# Power_board_2.net
KiCad netlist of a schematic drawn in Altium Designer
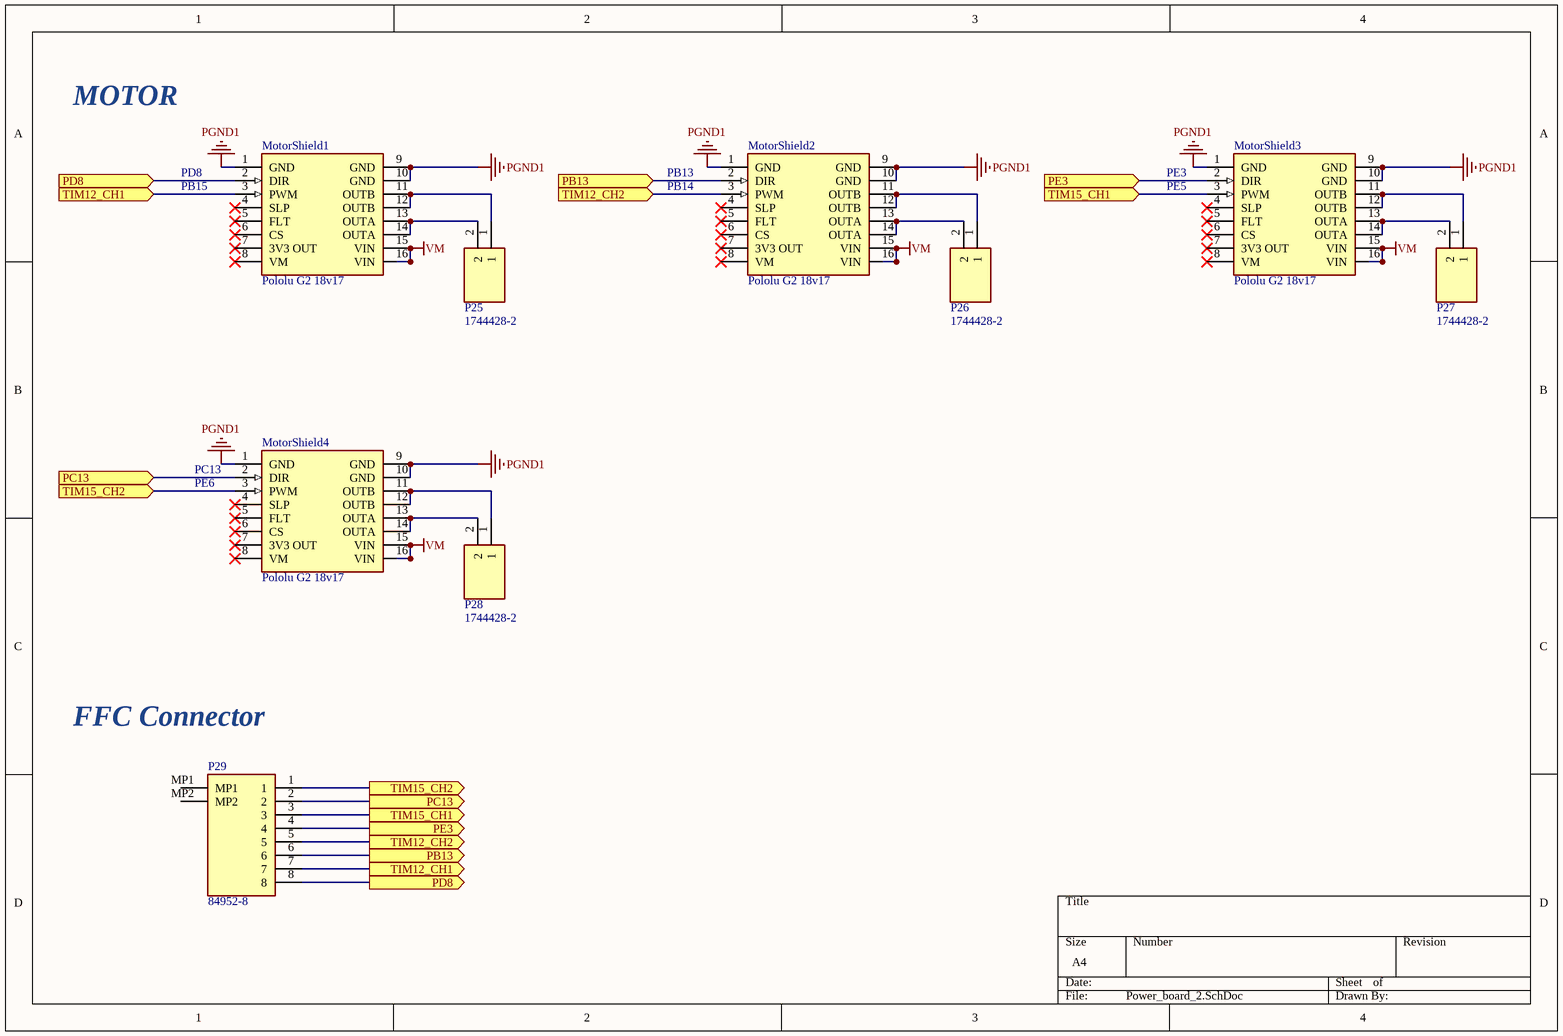
[diagram p0: Power_board_2.SchDoc]

(export (version "E")
  (design (tool "Eeschema 10.0.6"))
  (components
    (comp (ref "MotorShield1")
      (value "Pololu G2 18v17")
      (footprint "SamacSys:Pololu G218V17")
      (description "DC Motor Driver")
      (libsource (lib "SamacSys") (part "Pololu G2 18v17"))
    )
    (comp (ref "MotorShield2")
      (value "Pololu G2 18v17")
      (footprint "SamacSys:Pololu G218V17")
      (description "DC Motor Driver")
      (libsource (lib "SamacSys") (part "Pololu G2 18v17"))
    )
    (comp (ref "MotorShield3")
      (value "Pololu G2 18v17")
      (footprint "SamacSys:Pololu G218V17")
      (description "DC Motor Driver")
      (libsource (lib "SamacSys") (part "Pololu G2 18v17"))
    )
    (comp (ref "MotorShield4")
      (value "Pololu G2 18v17")
      (footprint "SamacSys:Pololu G218V17")
      (description "DC Motor Driver")
      (libsource (lib "SamacSys") (part "Pololu G2 18v17"))
    )
    (comp (ref "P25")
      (value "1744428-2")
      (footprint "SamacSys:17444282")
      (description "Connector")
      (fields (field (name "MOUSER PART NUMBER") "571-1744428-2"))
      (libsource (lib "*") (part "1744428-2"))
    )
    (comp (ref "P26")
      (value "1744428-2")
      (footprint "SamacSys:17444282")
      (description "Connector")
      (fields (field (name "MOUSER PART NUMBER") "571-1744428-2"))
      (libsource (lib "*") (part "1744428-2"))
    )
    (comp (ref "P27")
      (value "1744428-2")
      (footprint "SamacSys:17444282")
      (description "Connector")
      (fields (field (name "MOUSER PART NUMBER") "571-1744428-2"))
      (libsource (lib "*") (part "1744428-2"))
    )
    (comp (ref "P28")
      (value "1744428-2")
      (footprint "SamacSys:17444282")
      (description "Connector")
      (fields (field (name "MOUSER PART NUMBER") "571-1744428-2"))
      (libsource (lib "*") (part "1744428-2"))
    )
    (comp (ref "P29")
      (value "84952-8")
      (footprint "SamacSys:849528")
      (description "Connector")
      (fields (field (name "MOUSER PART NUMBER") "571-84952-8"))
      (libsource (lib "*") (part "84952-8"))
    )
  )
  (nets
    (net (code "1") (name "/PB13") (class "Default")
      (node (ref "MotorShield2") (pin "2") (pinfunction "DIR_2") (pintype "input"))
      (node (ref "P29") (pin "6") (pinfunction "6_6") (pintype "passive"))
    )
    (net (code "2") (name "/PC13") (class "Default")
      (node (ref "MotorShield4") (pin "2") (pinfunction "DIR_2") (pintype "input"))
      (node (ref "P29") (pin "2") (pinfunction "2_2") (pintype "passive"))
    )
    (net (code "3") (name "/PD8") (class "Default")
      (node (ref "MotorShield1") (pin "2") (pinfunction "DIR_2") (pintype "input"))
      (node (ref "P29") (pin "8") (pinfunction "8_8") (pintype "passive"))
    )
    (net (code "4") (name "/PE3") (class "Default")
      (node (ref "MotorShield3") (pin "2") (pinfunction "DIR_2") (pintype "input"))
      (node (ref "P29") (pin "4") (pinfunction "4_4") (pintype "passive"))
    )
    (net (code "5") (name "/TIM12_CH1") (class "Default")
      (node (ref "MotorShield1") (pin "3") (pinfunction "PWM_3") (pintype "input"))
      (node (ref "P29") (pin "7") (pinfunction "7_7") (pintype "passive"))
    )
    (net (code "6") (name "/TIM12_CH2") (class "Default")
      (node (ref "MotorShield2") (pin "3") (pinfunction "PWM_3") (pintype "input"))
      (node (ref "P29") (pin "5") (pinfunction "5_5") (pintype "passive"))
    )
    (net (code "7") (name "/TIM15_CH1") (class "Default")
      (node (ref "MotorShield3") (pin "3") (pinfunction "PWM_3") (pintype "input"))
      (node (ref "P29") (pin "3") (pinfunction "3_3") (pintype "passive"))
    )
    (net (code "8") (name "/TIM15_CH2") (class "Default")
      (node (ref "MotorShield4") (pin "3") (pinfunction "PWM_3") (pintype "input"))
      (node (ref "P29") (pin "1") (pinfunction "1_1") (pintype "passive"))
    )
    (net (code "9") (name "Net-(MotorShield1-OUTA-Pad13)") (class "Default")
      (node (ref "MotorShield1") (pin "13") (pinfunction "OUTA_13") (pintype "tri_state"))
      (node (ref "MotorShield1") (pin "14") (pinfunction "OUTA_14") (pintype "tri_state"))
      (node (ref "P25") (pin "2") (pinfunction "2_2") (pintype "passive"))
    )
    (net (code "10") (name "Net-(MotorShield1-OUTB-Pad11)") (class "Default")
      (node (ref "MotorShield1") (pin "11") (pinfunction "OUTB_11") (pintype "tri_state"))
      (node (ref "MotorShield1") (pin "12") (pinfunction "OUTB_12") (pintype "tri_state"))
      (node (ref "P25") (pin "1") (pinfunction "1_1") (pintype "passive"))
    )
    (net (code "11") (name "Net-(MotorShield2-OUTA-Pad13)") (class "Default")
      (node (ref "MotorShield2") (pin "13") (pinfunction "OUTA_13") (pintype "tri_state"))
      (node (ref "MotorShield2") (pin "14") (pinfunction "OUTA_14") (pintype "tri_state"))
      (node (ref "P26") (pin "2") (pinfunction "2_2") (pintype "passive"))
    )
    (net (code "12") (name "Net-(MotorShield2-OUTB-Pad11)") (class "Default")
      (node (ref "MotorShield2") (pin "11") (pinfunction "OUTB_11") (pintype "tri_state"))
      (node (ref "MotorShield2") (pin "12") (pinfunction "OUTB_12") (pintype "tri_state"))
      (node (ref "P26") (pin "1") (pinfunction "1_1") (pintype "passive"))
    )
    (net (code "13") (name "Net-(MotorShield3-OUTA-Pad13)") (class "Default")
      (node (ref "MotorShield3") (pin "13") (pinfunction "OUTA_13") (pintype "tri_state"))
      (node (ref "MotorShield3") (pin "14") (pinfunction "OUTA_14") (pintype "tri_state"))
      (node (ref "P27") (pin "2") (pinfunction "2_2") (pintype "passive"))
    )
    (net (code "14") (name "Net-(MotorShield3-OUTB-Pad11)") (class "Default")
      (node (ref "MotorShield3") (pin "11") (pinfunction "OUTB_11") (pintype "tri_state"))
      (node (ref "MotorShield3") (pin "12") (pinfunction "OUTB_12") (pintype "tri_state"))
      (node (ref "P27") (pin "1") (pinfunction "1_1") (pintype "passive"))
    )
    (net (code "15") (name "Net-(MotorShield4-OUTA-Pad13)") (class "Default")
      (node (ref "MotorShield4") (pin "13") (pinfunction "OUTA_13") (pintype "tri_state"))
      (node (ref "MotorShield4") (pin "14") (pinfunction "OUTA_14") (pintype "tri_state"))
      (node (ref "P28") (pin "2") (pinfunction "2_2") (pintype "passive"))
    )
    (net (code "16") (name "Net-(MotorShield4-OUTB-Pad11)") (class "Default")
      (node (ref "MotorShield4") (pin "11") (pinfunction "OUTB_11") (pintype "tri_state"))
      (node (ref "MotorShield4") (pin "12") (pinfunction "OUTB_12") (pintype "tri_state"))
      (node (ref "P28") (pin "1") (pinfunction "1_1") (pintype "passive"))
    )
    (net (code "17") (name "PGND1") (class "Default")
      (node (ref "MotorShield1") (pin "1") (pinfunction "GND_1") (pintype "tri_state"))
      (node (ref "MotorShield1") (pin "10") (pinfunction "GND_10") (pintype "tri_state"))
      (node (ref "MotorShield1") (pin "9") (pinfunction "GND_9") (pintype "passive"))
      (node (ref "MotorShield2") (pin "1") (pinfunction "GND_1") (pintype "tri_state"))
      (node (ref "MotorShield2") (pin "10") (pinfunction "GND_10") (pintype "tri_state"))
      (node (ref "MotorShield2") (pin "9") (pinfunction "GND_9") (pintype "passive"))
      (node (ref "MotorShield3") (pin "1") (pinfunction "GND_1") (pintype "tri_state"))
      (node (ref "MotorShield3") (pin "10") (pinfunction "GND_10") (pintype "tri_state"))
      (node (ref "MotorShield3") (pin "9") (pinfunction "GND_9") (pintype "passive"))
      (node (ref "MotorShield4") (pin "1") (pinfunction "GND_1") (pintype "tri_state"))
      (node (ref "MotorShield4") (pin "10") (pinfunction "GND_10") (pintype "tri_state"))
      (node (ref "MotorShield4") (pin "9") (pinfunction "GND_9") (pintype "passive"))
    )
    (net (code "18") (name "VM") (class "Default")
      (node (ref "MotorShield1") (pin "15") (pinfunction "VIN_15") (pintype "power_in"))
      (node (ref "MotorShield1") (pin "16") (pinfunction "VIN_16") (pintype "power_in"))
      (node (ref "MotorShield2") (pin "15") (pinfunction "VIN_15") (pintype "power_in"))
      (node (ref "MotorShield2") (pin "16") (pinfunction "VIN_16") (pintype "power_in"))
      (node (ref "MotorShield3") (pin "15") (pinfunction "VIN_15") (pintype "power_in"))
      (node (ref "MotorShield3") (pin "16") (pinfunction "VIN_16") (pintype "power_in"))
      (node (ref "MotorShield4") (pin "15") (pinfunction "VIN_15") (pintype "power_in"))
      (node (ref "MotorShield4") (pin "16") (pinfunction "VIN_16") (pintype "power_in"))
    )
    (net (code "19") (name "unconnected-(MotorShield1-3V3_OUT-Pad7)") (class "Default")
      (node (ref "MotorShield1") (pin "7") (pinfunction "3V3_OUT_7") (pintype "passive+no_connect"))
    )
    (net (code "20") (name "unconnected-(MotorShield1-CS-Pad6)") (class "Default")
      (node (ref "MotorShield1") (pin "6") (pinfunction "CS_6") (pintype "passive+no_connect"))
    )
    (net (code "21") (name "unconnected-(MotorShield1-FLT-Pad5)") (class "Default")
      (node (ref "MotorShield1") (pin "5") (pinfunction "FLT_5") (pintype "passive+no_connect"))
    )
    (net (code "22") (name "unconnected-(MotorShield1-SLP-Pad4)") (class "Default")
      (node (ref "MotorShield1") (pin "4") (pinfunction "SLP_4") (pintype "passive+no_connect"))
    )
    (net (code "23") (name "unconnected-(MotorShield1-VM-Pad8)") (class "Default")
      (node (ref "MotorShield1") (pin "8") (pinfunction "VM_8") (pintype "power_in+no_connect"))
    )
    (net (code "24") (name "unconnected-(MotorShield2-3V3_OUT-Pad7)") (class "Default")
      (node (ref "MotorShield2") (pin "7") (pinfunction "3V3_OUT_7") (pintype "passive+no_connect"))
    )
    (net (code "25") (name "unconnected-(MotorShield2-CS-Pad6)") (class "Default")
      (node (ref "MotorShield2") (pin "6") (pinfunction "CS_6") (pintype "passive+no_connect"))
    )
    (net (code "26") (name "unconnected-(MotorShield2-FLT-Pad5)") (class "Default")
      (node (ref "MotorShield2") (pin "5") (pinfunction "FLT_5") (pintype "passive+no_connect"))
    )
    (net (code "27") (name "unconnected-(MotorShield2-SLP-Pad4)") (class "Default")
      (node (ref "MotorShield2") (pin "4") (pinfunction "SLP_4") (pintype "passive+no_connect"))
    )
    (net (code "28") (name "unconnected-(MotorShield2-VM-Pad8)") (class "Default")
      (node (ref "MotorShield2") (pin "8") (pinfunction "VM_8") (pintype "power_in+no_connect"))
    )
    (net (code "29") (name "unconnected-(MotorShield3-3V3_OUT-Pad7)") (class "Default")
      (node (ref "MotorShield3") (pin "7") (pinfunction "3V3_OUT_7") (pintype "passive+no_connect"))
    )
    (net (code "30") (name "unconnected-(MotorShield3-CS-Pad6)") (class "Default")
      (node (ref "MotorShield3") (pin "6") (pinfunction "CS_6") (pintype "passive+no_connect"))
    )
    (net (code "31") (name "unconnected-(MotorShield3-FLT-Pad5)") (class "Default")
      (node (ref "MotorShield3") (pin "5") (pinfunction "FLT_5") (pintype "passive+no_connect"))
    )
    (net (code "32") (name "unconnected-(MotorShield3-SLP-Pad4)") (class "Default")
      (node (ref "MotorShield3") (pin "4") (pinfunction "SLP_4") (pintype "passive+no_connect"))
    )
    (net (code "33") (name "unconnected-(MotorShield3-VM-Pad8)") (class "Default")
      (node (ref "MotorShield3") (pin "8") (pinfunction "VM_8") (pintype "power_in+no_connect"))
    )
    (net (code "34") (name "unconnected-(MotorShield4-3V3_OUT-Pad7)") (class "Default")
      (node (ref "MotorShield4") (pin "7") (pinfunction "3V3_OUT_7") (pintype "passive+no_connect"))
    )
    (net (code "35") (name "unconnected-(MotorShield4-CS-Pad6)") (class "Default")
      (node (ref "MotorShield4") (pin "6") (pinfunction "CS_6") (pintype "passive+no_connect"))
    )
    (net (code "36") (name "unconnected-(MotorShield4-FLT-Pad5)") (class "Default")
      (node (ref "MotorShield4") (pin "5") (pinfunction "FLT_5") (pintype "passive+no_connect"))
    )
    (net (code "37") (name "unconnected-(MotorShield4-SLP-Pad4)") (class "Default")
      (node (ref "MotorShield4") (pin "4") (pinfunction "SLP_4") (pintype "passive+no_connect"))
    )
    (net (code "38") (name "unconnected-(MotorShield4-VM-Pad8)") (class "Default")
      (node (ref "MotorShield4") (pin "8") (pinfunction "VM_8") (pintype "power_in+no_connect"))
    )
    (net (code "39") (name "unconnected-(P29-PadMP1)") (class "Default")
      (node (ref "P29") (pin "MP1") (pinfunction "MP1_MP1") (pintype "passive"))
    )
    (net (code "40") (name "unconnected-(P29-PadMP2)") (class "Default")
      (node (ref "P29") (pin "MP2") (pinfunction "MP2_MP2") (pintype "passive"))
    )
  )
)
